# Top.net
KiCad netlist of a schematic drawn in Altium Designer
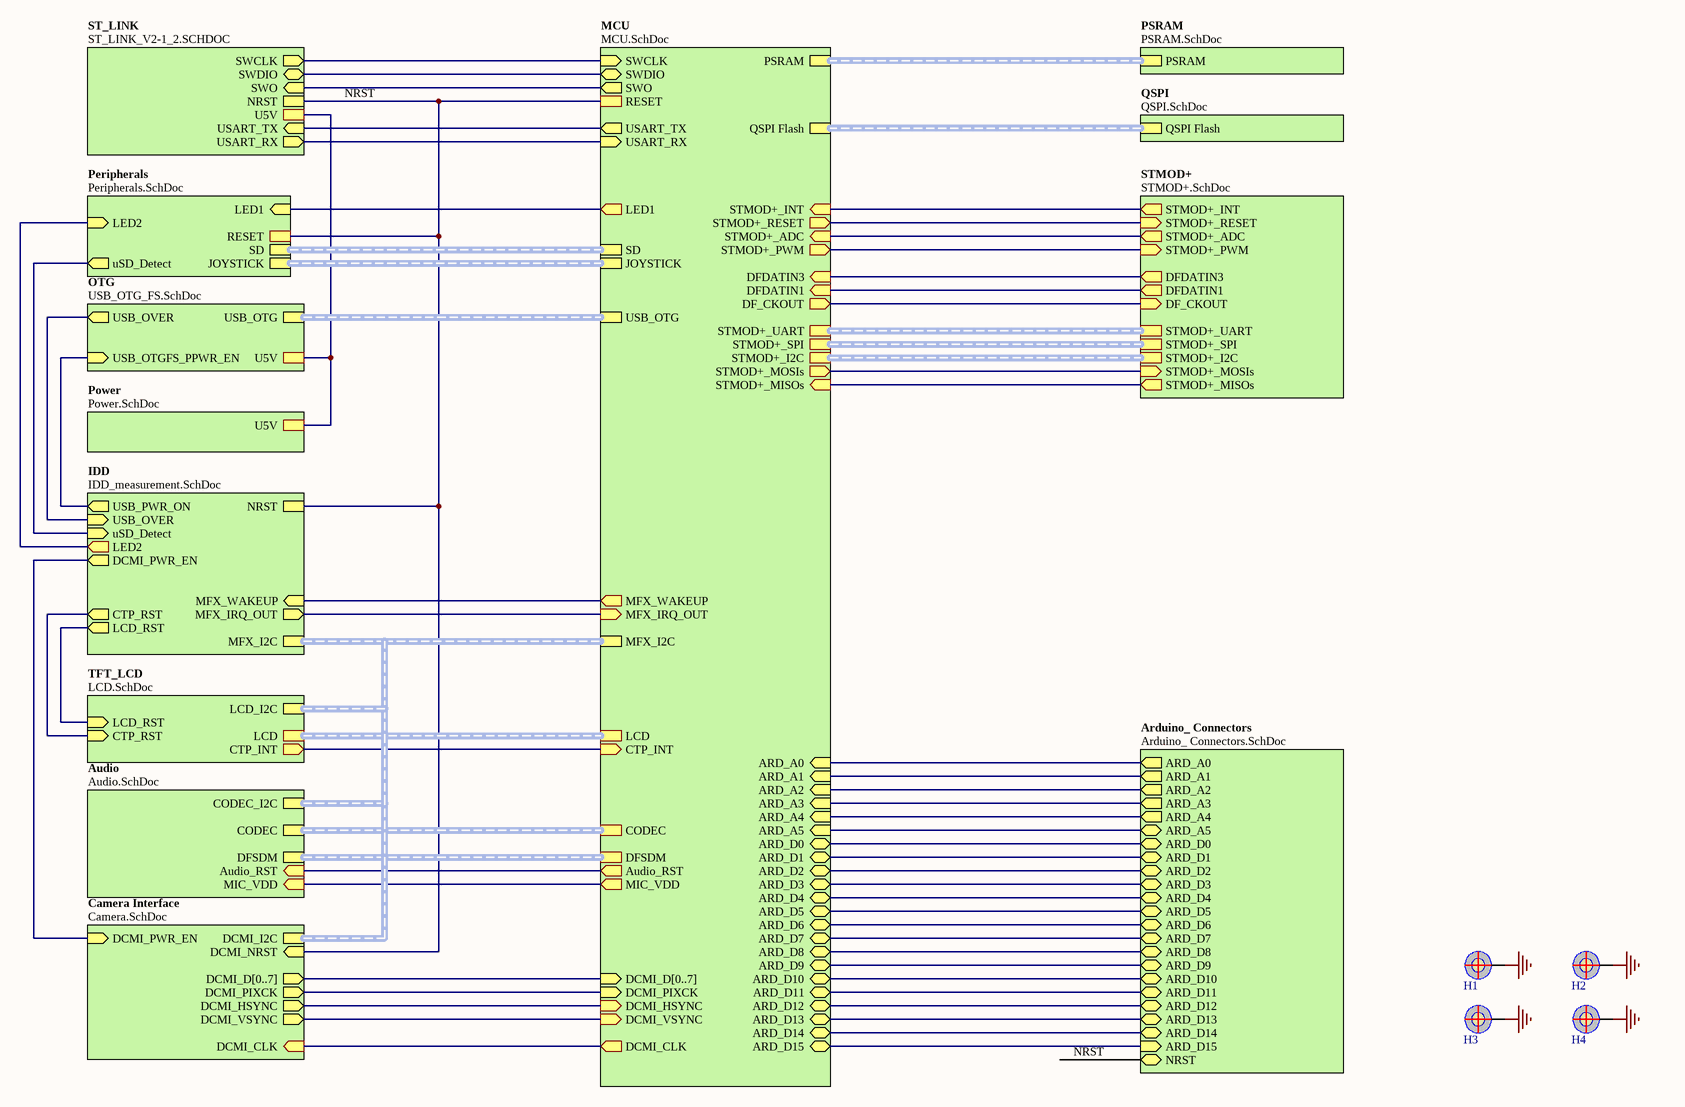
[diagram p0: Top.SchDoc]

(export (version "E")
  (design (tool "Eeschema 10.0.6"))
  (components
    (comp (ref "H1")
      (value "POSITION HOLE")
      (footprint "Hole_C7d3r5")
      (libsource (lib "mb1045") (part "POSITION HOLE"))
    )
    (comp (ref "H2")
      (value "POSITION HOLE")
      (footprint "Hole_C7d3r5")
      (libsource (lib "mb1045") (part "POSITION HOLE"))
    )
    (comp (ref "H3")
      (value "POSITION HOLE")
      (footprint "Hole_C7d3r5")
      (libsource (lib "mb1045") (part "POSITION HOLE"))
    )
    (comp (ref "H4")
      (value "POSITION HOLE")
      (footprint "Hole_C7d3r5")
      (libsource (lib "mb1045") (part "POSITION HOLE"))
    )
  )
  (nets
    (net (code "69") (name "GND") (class "Default")
      (node (ref "H1") (pin "1") (pinfunction "1_1") (pintype "passive"))
      (node (ref "H2") (pin "1") (pinfunction "1_1") (pintype "passive"))
      (node (ref "H3") (pin "1") (pinfunction "1_1") (pintype "passive"))
      (node (ref "H4") (pin "1") (pinfunction "1_1") (pintype "passive"))
    )
  )
)
